# Brunnenwasseradaper.net
KiCad netlist of a schematic drawn in EAGLE
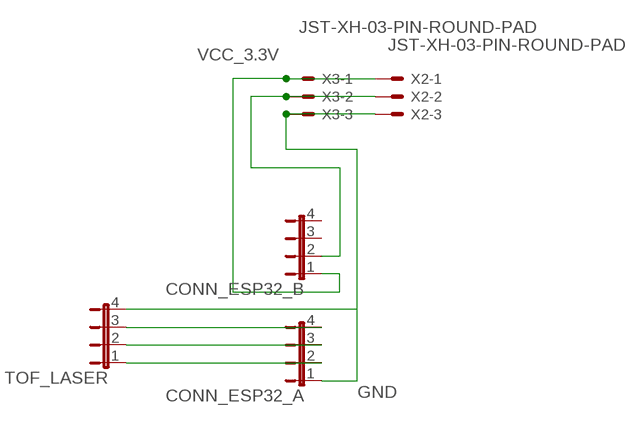
[diagram p0: schematic, sheet 1]

(export (version "E")
  (design (tool "Eeschema 10.0.6"))
  (components
    (comp (ref "CONN_ESP32_A")
      (value "JP4E")
      (footprint "eagle-import:JP4")
      (libsource (lib "eagle-import") (part "JP4E"))
    )
    (comp (ref "CONN_ESP32_B")
      (value "JP4E")
      (footprint "eagle-import:JP4")
      (libsource (lib "eagle-import") (part "JP4E"))
    )
    (comp (ref "TOF_LASER")
      (value "JP4E")
      (footprint "eagle-import:JP4")
      (libsource (lib "eagle-import") (part "JP4E"))
    )
    (comp (ref "X2")
      (value "JST-XH-03-PIN-ROUND-PAD")
      (footprint "eagle-import:JST-XH-03-PACKAGE-ROUND-PAD")
      (libsource (lib "eagle-import") (part "JST-XH-03-PIN-ROUND-PAD"))
    )
    (comp (ref "X3")
      (value "JST-XH-03-PIN-ROUND-PAD")
      (footprint "eagle-import:JST-XH-03-PACKAGE-ROUND-PAD")
      (libsource (lib "eagle-import") (part "JST-XH-03-PIN-ROUND-PAD"))
    )
  )
  (nets
    (net (code "1") (name "/GND") (class "Default")
      (node (ref "CONN_ESP32_A") (pin "1") (pinfunction "1_1") (pintype "passive"))
      (node (ref "TOF_LASER") (pin "4") (pinfunction "4_4") (pintype "passive"))
      (node (ref "X2") (pin "3") (pinfunction "S_3") (pintype "passive"))
      (node (ref "X3") (pin "3") (pinfunction "S_3") (pintype "passive"))
    )
    (net (code "2") (name "/VCC_3.3V") (class "Default")
      (node (ref "CONN_ESP32_B") (pin "1") (pinfunction "1_1") (pintype "passive"))
      (node (ref "X2") (pin "1") (pinfunction "S_1") (pintype "passive"))
      (node (ref "X3") (pin "1") (pinfunction "S_1") (pintype "passive"))
    )
    (net (code "3") (name "Net-(CONN_ESP32_A-Pad2)") (class "Default")
      (node (ref "CONN_ESP32_A") (pin "2") (pinfunction "2_2") (pintype "passive"))
      (node (ref "TOF_LASER") (pin "1") (pinfunction "1_1") (pintype "passive"))
    )
    (net (code "4") (name "Net-(CONN_ESP32_A-Pad3)") (class "Default")
      (node (ref "CONN_ESP32_A") (pin "3") (pinfunction "3_3") (pintype "passive"))
      (node (ref "TOF_LASER") (pin "2") (pinfunction "2_2") (pintype "passive"))
    )
    (net (code "5") (name "Net-(CONN_ESP32_A-Pad4)") (class "Default")
      (node (ref "CONN_ESP32_A") (pin "4") (pinfunction "4_4") (pintype "passive"))
      (node (ref "TOF_LASER") (pin "3") (pinfunction "3_3") (pintype "passive"))
    )
    (net (code "6") (name "Net-(X2B-S)") (class "Default")
      (node (ref "CONN_ESP32_B") (pin "2") (pinfunction "2_2") (pintype "passive"))
      (node (ref "X2") (pin "2") (pinfunction "S_2") (pintype "passive"))
      (node (ref "X3") (pin "2") (pinfunction "S_2") (pintype "passive"))
    )
    (net (code "7") (name "unconnected-(CONN_ESP32_B-Pad3)") (class "Default")
      (node (ref "CONN_ESP32_B") (pin "3") (pinfunction "3_3") (pintype "passive"))
    )
    (net (code "8") (name "unconnected-(CONN_ESP32_B-Pad4)") (class "Default")
      (node (ref "CONN_ESP32_B") (pin "4") (pinfunction "4_4") (pintype "passive"))
    )
  )
)
